# MCU.net
KiCad netlist of a schematic drawn in Altium Designer
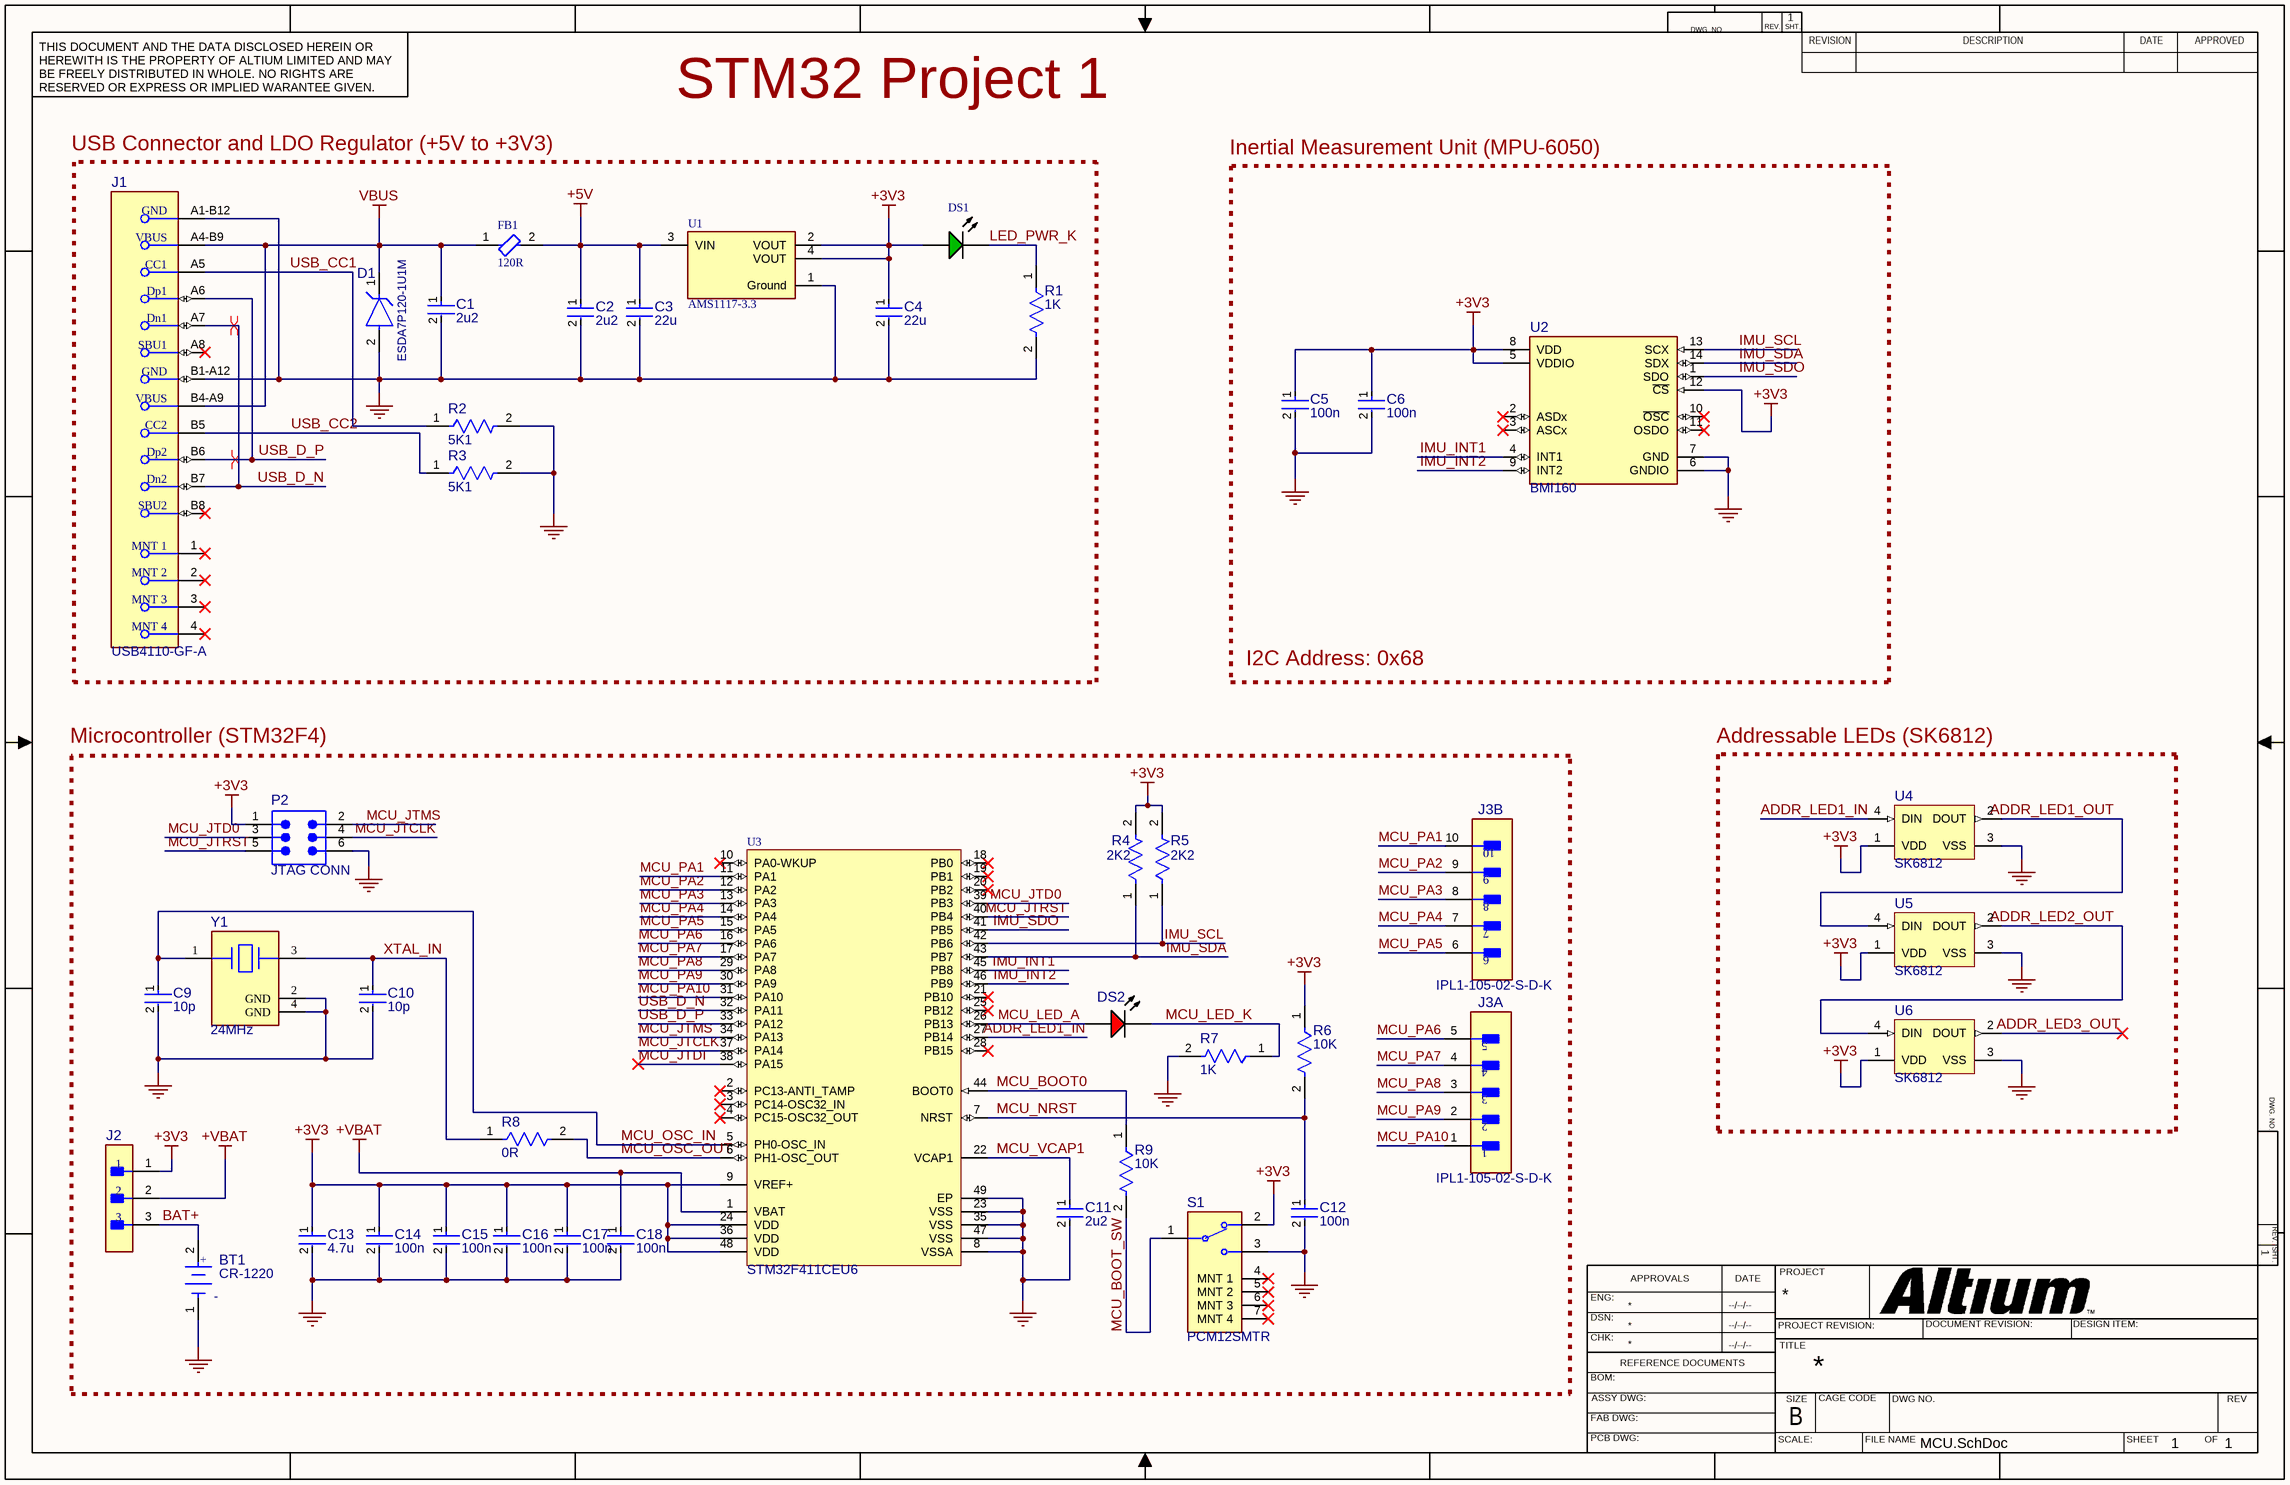
[diagram p0: MCU.SchDoc]

(export (version "E")
  (design (tool "Eeschema 10.0.6"))
  (components
    (comp (ref "BT1")
      (value "CR-1220")
      (footprint "FP-S8411-45R-MFG")
      (description "BATTERY HOLDER COIN 12MM SMD")
      (libsource (lib "Altium Content Vault") (part "60d3b5b901a8747834971d0eb8cf3fd"))
    )
    (comp (ref "C1")
      (value "2u2")
      (footprint "FP-0805-L_2_01_0_2-W_1_25-IPC_B")
      (description "General Purpose Ceramic Capacitor, 0805, 2.2uF, 10%, X5R, 15%, 10V")
      (fields (field (name "VOLTAGE") "10V") (field (name "TOLERANCE") "10%"))
      (libsource (lib "Altium Content Vault") (part "b4654b650e69147ec39a6b967a45e02"))
    )
    (comp (ref "C2")
      (value "2u2")
      (footprint "FP-0805-L_2_01_0_2-W_1_25-IPC_B")
      (description "General Purpose Ceramic Capacitor, 0805, 2.2uF, 10%, X5R, 15%, 10V")
      (fields (field (name "VOLTAGE") "10V") (field (name "TOLERANCE") "10%"))
      (libsource (lib "Altium Content Vault") (part "b4654b650e69147ec39a6b967a45e02"))
    )
    (comp (ref "C3")
      (value "22u")
      (footprint "FP-CC0805-0_85-MFG")
      (description "CAP CER 0.1UF 16V X7R 0805")
      (fields
        (field (name "MANUFACTURER PART NUMBER") "CC0805KRX7R7BB104")
        (field (name "MANUFACTURER") "Yageo")
      )
      (libsource (lib "Altium Content Vault") (part "11868f565c42a9108669ba33697ecf6"))
    )
    (comp (ref "C4")
      (value "22u")
      (footprint "FP-CC0805-0_85-MFG")
      (description "CAP CER 0.1UF 16V X7R 0805")
      (fields
        (field (name "MANUFACTURER PART NUMBER") "CC0805KRX7R7BB104")
        (field (name "MANUFACTURER") "Yageo")
      )
      (libsource (lib "Altium Content Vault") (part "11868f565c42a9108669ba33697ecf6"))
    )
    (comp (ref "C5")
      (value "100n")
      (footprint "FP-CC0805-0_85-MFG")
      (description "CAP CER 0.1UF 16V X7R 0805")
      (fields
        (field (name "MANUFACTURER PART NUMBER") "CC0805KRX7R7BB104")
        (field (name "MANUFACTURER") "Yageo")
      )
      (libsource (lib "Altium Content Vault") (part "11868f565c42a9108669ba33697ecf6"))
    )
    (comp (ref "C6")
      (value "100n")
      (footprint "FP-CC0805-0_85-MFG")
      (description "CAP CER 0.1UF 16V X7R 0805")
      (fields
        (field (name "MANUFACTURER PART NUMBER") "CC0805KRX7R7BB104")
        (field (name "MANUFACTURER") "Yageo")
      )
      (libsource (lib "Altium Content Vault") (part "11868f565c42a9108669ba33697ecf6"))
    )
    (comp (ref "C9")
      (value "10p")
      (footprint "FP-CC0805-0_85-MFG")
      (description "CAP CER 0.1UF 16V X7R 0805")
      (fields
        (field (name "MANUFACTURER PART NUMBER") "CC0805KRX7R7BB104")
        (field (name "MANUFACTURER") "Yageo")
      )
      (libsource (lib "Altium Content Vault") (part "11868f565c42a9108669ba33697ecf6"))
    )
    (comp (ref "C10")
      (value "10p")
      (footprint "FP-CC0805-0_85-MFG")
      (description "CAP CER 0.1UF 16V X7R 0805")
      (fields
        (field (name "MANUFACTURER PART NUMBER") "CC0805KRX7R7BB104")
        (field (name "MANUFACTURER") "Yageo")
      )
      (libsource (lib "Altium Content Vault") (part "11868f565c42a9108669ba33697ecf6"))
    )
    (comp (ref "C11")
      (value "2u2")
      (footprint "FP-0805-L_2_01_0_2-W_1_25-IPC_B")
      (description "General Purpose Ceramic Capacitor, 0805, 2.2uF, 10%, X5R, 15%, 10V")
      (fields (field (name "VOLTAGE") "10V") (field (name "TOLERANCE") "10%"))
      (libsource (lib "Altium Content Vault") (part "b4654b650e69147ec39a6b967a45e02"))
    )
    (comp (ref "C12")
      (value "100n")
      (footprint "FP-CC0805-0_85-MFG")
      (description "CAP CER 0.1UF 16V X7R 0805")
      (fields
        (field (name "MANUFACTURER PART NUMBER") "CC0805KRX7R7BB104")
        (field (name "MANUFACTURER") "Yageo")
      )
      (libsource (lib "Altium Content Vault") (part "11868f565c42a9108669ba33697ecf6"))
    )
    (comp (ref "C13")
      (value "4.7u")
      (footprint "FP-0805-L_2_01_0_2-W_1_25-MFG")
      (description "General Purpose Ceramic Capacitor, 0805, 4.7uF, 10%, X7R, 15%, 16V")
      (fields (field (name "VOLTAGE") "10V") (field (name "TOLERANCE") "10%"))
      (libsource (lib "Altium Content Vault") (part "02cd4be3c70576c341d710602a673aa"))
    )
    (comp (ref "C14")
      (value "100n")
      (footprint "FP-CC0805-0_85-MFG")
      (description "CAP CER 0.1UF 16V X7R 0805")
      (fields
        (field (name "MANUFACTURER PART NUMBER") "CC0805KRX7R7BB104")
        (field (name "MANUFACTURER") "Yageo")
      )
      (libsource (lib "Altium Content Vault") (part "11868f565c42a9108669ba33697ecf6"))
    )
    (comp (ref "C15")
      (value "100n")
      (footprint "FP-CC0805-0_85-MFG")
      (description "CAP CER 0.1UF 16V X7R 0805")
      (fields
        (field (name "MANUFACTURER PART NUMBER") "CC0805KRX7R7BB104")
        (field (name "MANUFACTURER") "Yageo")
      )
      (libsource (lib "Altium Content Vault") (part "11868f565c42a9108669ba33697ecf6"))
    )
    (comp (ref "C16")
      (value "100n")
      (footprint "FP-CC0805-0_85-MFG")
      (description "CAP CER 0.1UF 16V X7R 0805")
      (fields
        (field (name "MANUFACTURER PART NUMBER") "CC0805KRX7R7BB104")
        (field (name "MANUFACTURER") "Yageo")
      )
      (libsource (lib "Altium Content Vault") (part "11868f565c42a9108669ba33697ecf6"))
    )
    (comp (ref "C17")
      (value "100n")
      (footprint "FP-CC0805-0_85-MFG")
      (description "CAP CER 0.1UF 16V X7R 0805")
      (fields
        (field (name "MANUFACTURER PART NUMBER") "CC0805KRX7R7BB104")
        (field (name "MANUFACTURER") "Yageo")
      )
      (libsource (lib "Altium Content Vault") (part "11868f565c42a9108669ba33697ecf6"))
    )
    (comp (ref "C18")
      (value "100n")
      (footprint "FP-CC0805-0_85-MFG")
      (description "CAP CER 0.1UF 16V X7R 0805")
      (fields
        (field (name "MANUFACTURER PART NUMBER") "CC0805KRX7R7BB104")
        (field (name "MANUFACTURER") "Yageo")
      )
      (libsource (lib "Altium Content Vault") (part "11868f565c42a9108669ba33697ecf6"))
    )
    (comp (ref "D1")
      (value "ESDA7P120-1U1M")
      (footprint "FP-QFN1610-MFG")
      (description "TVS DIODE 5.5V 11.5V 1610")
      (fields
        (field (name "MANUFACTURER") "STMicroelectronics")
        (field (name "OCTOPART") "https://octopart.com/esda7p120-1u1m-stmicroelectronics-80927196")
      )
      (libsource (lib "Altium Content Vault") (part "f813f71cba58e380607f5dd3caf9714"))
    )
    (comp (ref "DS1")
      (value "1K")
      (footprint "AVAG-HSMX-C170_V")
      (description "Chip LED, Green, 2.2 V, -40 to 85 degC, 2-Pin SMD, Pb-Free, Tape and Reel")
      (fields (field (name "MANUFACTURER") "Avago"))
      (libsource (lib "Altium Content Vault") (part "LED_GREEN_A1K2-2"))
    )
    (comp (ref "DS2")
      (value "LTST-C170KRKT")
      (footprint "LTST-C170KRKT_V")
      (description "LED Red, 75 mW, 54 mcd, -55 to 85 degC, 2-Pin SMD, RoHS, Tape and Reel")
      (fields (field (name "MANUFACTURER") "Lite-On"))
      (libsource (lib "Altium Content Vault") (part "LED-RED-AK-2"))
    )
    (comp (ref "FB1")
      (value "120R")
      (footprint "FP-BLM21-0_2-t0_85-e0_5-IPC_A")
      (description "FERRITE BEAD 120 OHM 0805 1LN")
      (fields (field (name "TOLERANCE") "25%"))
      (libsource (lib "Altium Content Vault") (part "5f30dd21d616792df468990f7003faa"))
    )
    (comp (ref "J1")
      (value "USB4110-GF-A")
      (footprint "FP-USB4110-GF-A-MFG")
      (description "CONN USB 2.0 TYPE-C R/A SMT")
      (fields
        (field (name "OCTOPART") "https://octopart.com/usb4110-gf-a-gct-103941985")
        (field (name "MANUFACTURER") "GCT")
      )
      (libsource (lib "Altium Content Vault") (part "e23f2b38bb3c3f98e683ebab9ede730"))
    )
    (comp (ref "J2")
      (value "5-146128-1")
      (footprint "FP-5-146128-1-MFG")
      (description "CONN HEADER SMD 3POS 2.54MM")
      (fields
        (field (name "MANUFACTURER") "TE")
        (field (name "OCTOPART") "https://octopart.com/5-146128-1-te+connectivity-40948200")
      )
      (libsource (lib "Altium Content Vault") (part "0d3f023dd272f625e17a2be33dea85f"))
    )
    (comp (ref "J3")
      (value "IPL1-105-02-S-D-K")
      (footprint "FP-IPL1-105-02-S-D-K-0")
      (description "5 Position 2 Row .100\" (2.54 mm) pitch connector")
      (libsource (lib "Altium Content Vault") (part "66d25172edd0fcb6412fc33dd95d2c2"))
    )
    (comp (ref "P2")
      (value "JTAG CONN")
      (footprint "61000621121")
      (libsource (lib "Altium Content Vault") (part "Header_Male_2R_06P"))
    )
    (comp (ref "R1")
      (value "1K")
      (footprint "FP-CRCW0805-e3-IPC_A")
      (description "RES Thick Film, 10kΩ, 1%, 0.125W, 100ppm/°C, 0805")
      (fields (field (name "TOLERANCE") "1%"))
      (libsource (lib "Altium Content Vault") (part "1029c3af85768c4190bb7ad29bc67b5"))
    )
    (comp (ref "R2")
      (value "5K1")
      (footprint "FP-CRCW0805-e3-IPC_A")
      (description "RES Thick Film, 10kΩ, 1%, 0.125W, 100ppm/°C, 0805")
      (fields (field (name "TOLERANCE") "1%"))
      (libsource (lib "Altium Content Vault") (part "1029c3af85768c4190bb7ad29bc67b5"))
    )
    (comp (ref "R3")
      (value "5K1")
      (footprint "FP-CRCW0805-e3-IPC_A")
      (description "RES Thick Film, 10kΩ, 1%, 0.125W, 100ppm/°C, 0805")
      (fields (field (name "TOLERANCE") "1%"))
      (libsource (lib "Altium Content Vault") (part "1029c3af85768c4190bb7ad29bc67b5"))
    )
    (comp (ref "R4")
      (value "2K2")
      (footprint "FP-CRCW0805-e3-IPC_A")
      (description "RES Thick Film, 10kΩ, 1%, 0.125W, 100ppm/°C, 0805")
      (fields (field (name "TOLERANCE") "1%"))
      (libsource (lib "Altium Content Vault") (part "1029c3af85768c4190bb7ad29bc67b5"))
    )
    (comp (ref "R5")
      (value "2K2")
      (footprint "FP-CRCW0805-e3-IPC_A")
      (description "RES Thick Film, 10kΩ, 1%, 0.125W, 100ppm/°C, 0805")
      (fields (field (name "TOLERANCE") "1%"))
      (libsource (lib "Altium Content Vault") (part "1029c3af85768c4190bb7ad29bc67b5"))
    )
    (comp (ref "R6")
      (value "10K")
      (footprint "FP-CRCW0805-e3-IPC_A")
      (description "RES Thick Film, 10kΩ, 1%, 0.125W, 100ppm/°C, 0805")
      (fields (field (name "TOLERANCE") "1%"))
      (libsource (lib "Altium Content Vault") (part "1029c3af85768c4190bb7ad29bc67b5"))
    )
    (comp (ref "R7")
      (value "1K")
      (footprint "FP-CRCW0805-e3-IPC_A")
      (description "RES Thick Film, 10kΩ, 1%, 0.125W, 100ppm/°C, 0805")
      (fields (field (name "TOLERANCE") "1%"))
      (libsource (lib "Altium Content Vault") (part "1029c3af85768c4190bb7ad29bc67b5"))
    )
    (comp (ref "R8")
      (value "0R")
      (footprint "FP-CRCW0805-e3-IPC_A")
      (description "RES Thick Film, 10kΩ, 1%, 0.125W, 100ppm/°C, 0805")
      (fields (field (name "TOLERANCE") "1%"))
      (libsource (lib "Altium Content Vault") (part "1029c3af85768c4190bb7ad29bc67b5"))
    )
    (comp (ref "R9")
      (value "10K")
      (footprint "FP-CRCW0805-e3-IPC_A")
      (description "RES Thick Film, 10kΩ, 1%, 0.125W, 100ppm/°C, 0805")
      (fields (field (name "TOLERANCE") "1%"))
      (libsource (lib "Altium Content Vault") (part "1029c3af85768c4190bb7ad29bc67b5"))
    )
    (comp (ref "S1")
      (value "PCM12SMTR")
      (footprint "FP-PCM12SMTR-MFG")
      (description "SWITCH SLIDE SPDT 300MA 6V")
      (libsource (lib "Altium Content Vault") (part "1a3f67d7e2b5469b171eeab59ffb4d2"))
    )
    (comp (ref "U1")
      (value "AMS1117-3.3")
      (footprint "FP-AMS1117-IPC_C")
      (description "LDO Voltage Regulators 1A, 3.3V")
      (fields
        (field (name "OCTOPART") "https://octopart.com/ams1117-3.3-advanced+monolithic+systems-25899300")
        (field (name "MANUFACTURER") "Advanced Monolithic Systems")
      )
      (libsource (lib "Altium Content Vault") (part "8bdbb5f8e77002000e30dd2845d0354"))
    )
    (comp (ref "U2")
      (value "BMI160")
      (footprint "FP-BMI160-MFG")
      (description "IMU ACCEL/GYRO I2C/SPI 14LGA")
      (libsource (lib "Altium Content Vault") (part "31c3d492c9327b72c063bbae4eb218e"))
    )
    (comp (ref "U3")
      (value "STM32F411CEU6")
      (footprint "STM-UFQFPN48_L")
      (libsource (lib "Altium Content Vault") (part "MC-ARM-STM32F411-UFQFPN48"))
    )
    (comp (ref "U4")
      (value "SK6812")
      (footprint "ADA-RGB-1655_V")
      (fields (field (name "MANUFACTURER") "Adafruit-Industries-LLC"))
      (libsource (lib "Altium Content Vault") (part "ADA-RGB-1655-4"))
    )
    (comp (ref "U5")
      (value "SK6812")
      (footprint "ADA-RGB-1655_V")
      (fields (field (name "MANUFACTURER") "Adafruit-Industries-LLC"))
      (libsource (lib "Altium Content Vault") (part "ADA-RGB-1655-4"))
    )
    (comp (ref "U6")
      (value "SK6812")
      (footprint "ADA-RGB-1655_V")
      (fields (field (name "MANUFACTURER") "Adafruit-Industries-LLC"))
      (libsource (lib "Altium Content Vault") (part "ADA-RGB-1655-4"))
    )
    (comp (ref "Y1")
      (value "24MHz")
      (footprint "FP-ABM8G-MFG")
      (description "Crystal 24MHz ±30ppm (Tol) ±30ppm (Stability) 10pF FUND 60Ω 4-Pin SMD T/R")
      (fields (field (name "TOLERANCE") "30ppm"))
      (libsource (lib "Altium Content Vault") (part "48e526d86b7f2615d98721063c72f49"))
    )
  )
  (nets
    (net (code "1") (name "+3V3") (class "Default")
      (node (ref "C13") (pin "1") (pinfunction "1_1") (pintype "passive"))
      (node (ref "C14") (pin "1") (pinfunction "1_1") (pintype "passive"))
      (node (ref "C15") (pin "1") (pinfunction "1_1") (pintype "passive"))
      (node (ref "C16") (pin "1") (pinfunction "1_1") (pintype "passive"))
      (node (ref "C17") (pin "1") (pinfunction "1_1") (pintype "passive"))
      (node (ref "C4") (pin "1") (pinfunction "1_1") (pintype "passive"))
      (node (ref "C5") (pin "1") (pinfunction "1_1") (pintype "passive"))
      (node (ref "C6") (pin "1") (pinfunction "1_1") (pintype "passive"))
      (node (ref "DS1") (pin "1") (pinfunction "A_1") (pintype "passive"))
      (node (ref "J2") (pin "1") (pinfunction "1_1") (pintype "passive"))
      (node (ref "P2") (pin "1") (pinfunction "1_1") (pintype "passive"))
      (node (ref "R4") (pin "2") (pinfunction "2_2") (pintype "passive"))
      (node (ref "R5") (pin "2") (pinfunction "2_2") (pintype "passive"))
      (node (ref "R6") (pin "1") (pinfunction "1_1") (pintype "passive"))
      (node (ref "S1") (pin "2") (pinfunction "2_2") (pintype "passive"))
      (node (ref "U1") (pin "2") (pinfunction "VOUT_2") (pintype "passive"))
      (node (ref "U1") (pin "4") (pinfunction "VOUT_4") (pintype "passive"))
      (node (ref "U2") (pin "12") (pinfunction "~{CS}_12") (pintype "input"))
      (node (ref "U2") (pin "5") (pinfunction "VDDIO_5") (pintype "power_in"))
      (node (ref "U2") (pin "8") (pinfunction "VDD_8") (pintype "power_in"))
      (node (ref "U3") (pin "24") (pinfunction "VDD_24") (pintype "power_in"))
      (node (ref "U3") (pin "36") (pinfunction "VDD_36") (pintype "power_in"))
      (node (ref "U3") (pin "48") (pinfunction "VDD_48") (pintype "power_in"))
      (node (ref "U3") (pin "9") (pinfunction "VREF+_9") (pintype "power_in"))
      (node (ref "U4") (pin "1") (pinfunction "VDD_1") (pintype "power_in"))
      (node (ref "U5") (pin "1") (pinfunction "VDD_1") (pintype "power_in"))
      (node (ref "U6") (pin "1") (pinfunction "VDD_1") (pintype "power_in"))
    )
    (net (code "2") (name "+5V") (class "Default")
      (node (ref "C2") (pin "1") (pinfunction "1_1") (pintype "passive"))
      (node (ref "C3") (pin "1") (pinfunction "1_1") (pintype "passive"))
      (node (ref "FB1") (pin "2") (pinfunction "2_2") (pintype "passive"))
      (node (ref "U1") (pin "3") (pinfunction "VIN_3") (pintype "power_in"))
    )
    (net (code "3") (name "+VBAT") (class "Default")
      (node (ref "C18") (pin "1") (pinfunction "1_1") (pintype "passive"))
      (node (ref "J2") (pin "2") (pinfunction "2_2") (pintype "passive"))
      (node (ref "U3") (pin "1") (pinfunction "VBAT_1") (pintype "power_in"))
    )
    (net (code "4") (name "/ADDR_LED1_IN") (class "Default")
      (node (ref "U3") (pin "27") (pinfunction "PB14_27") (pintype "bidirectional"))
      (node (ref "U4") (pin "4") (pinfunction "DIN_4") (pintype "input"))
    )
    (net (code "5") (name "/ADDR_LED1_OUT") (class "Default")
      (node (ref "U4") (pin "2") (pinfunction "DOUT_2") (pintype "output"))
      (node (ref "U5") (pin "4") (pinfunction "DIN_4") (pintype "input"))
    )
    (net (code "6") (name "/ADDR_LED2_OUT") (class "Default")
      (node (ref "U5") (pin "2") (pinfunction "DOUT_2") (pintype "output"))
      (node (ref "U6") (pin "4") (pinfunction "DIN_4") (pintype "input"))
    )
    (net (code "7") (name "/ADDR_LED3_OUT") (class "Default")
      (node (ref "U6") (pin "2") (pinfunction "DOUT_2") (pintype "output+no_connect"))
    )
    (net (code "8") (name "/BAT+") (class "Default")
      (node (ref "BT1") (pin "2") (pinfunction "A_2") (pintype "passive"))
      (node (ref "J2") (pin "3") (pinfunction "3_3") (pintype "passive"))
    )
    (net (code "9") (name "/IMU_INT1") (class "Default")
      (node (ref "U2") (pin "4") (pinfunction "INT1_4") (pintype "bidirectional"))
      (node (ref "U3") (pin "45") (pinfunction "PB8_45") (pintype "bidirectional"))
    )
    (net (code "10") (name "/IMU_INT2") (class "Default")
      (node (ref "U2") (pin "9") (pinfunction "INT2_9") (pintype "bidirectional"))
      (node (ref "U3") (pin "46") (pinfunction "PB9_46") (pintype "bidirectional"))
    )
    (net (code "11") (name "/IMU_SCL") (class "Default")
      (node (ref "R5") (pin "1") (pinfunction "1_1") (pintype "passive"))
      (node (ref "U2") (pin "13") (pinfunction "SCX_13") (pintype "input"))
      (node (ref "U3") (pin "42") (pinfunction "PB6_42") (pintype "bidirectional"))
    )
    (net (code "12") (name "/IMU_SDA") (class "Default")
      (node (ref "R4") (pin "1") (pinfunction "1_1") (pintype "passive"))
      (node (ref "U2") (pin "14") (pinfunction "SDX_14") (pintype "bidirectional"))
      (node (ref "U3") (pin "43") (pinfunction "PB7_43") (pintype "bidirectional"))
    )
    (net (code "13") (name "/IMU_SDO") (class "Default")
      (node (ref "U2") (pin "1") (pinfunction "SDO_1") (pintype "bidirectional"))
      (node (ref "U3") (pin "41") (pinfunction "PB5_41") (pintype "bidirectional"))
    )
    (net (code "14") (name "/LED_PWR_K") (class "Default")
      (node (ref "DS1") (pin "2") (pinfunction "K_2") (pintype "passive"))
      (node (ref "R1") (pin "1") (pinfunction "1_1") (pintype "passive"))
    )
    (net (code "15") (name "/MCU_BOOT0") (class "Default")
      (node (ref "R9") (pin "1") (pinfunction "1_1") (pintype "passive"))
      (node (ref "U3") (pin "44") (pinfunction "BOOT0_44") (pintype "input"))
    )
    (net (code "16") (name "/MCU_BOOT_SW") (class "Default")
      (node (ref "R9") (pin "2") (pinfunction "2_2") (pintype "passive"))
      (node (ref "S1") (pin "1") (pinfunction "1_1") (pintype "passive"))
    )
    (net (code "17") (name "/MCU_JTCLK") (class "Default")
      (node (ref "P2") (pin "4") (pinfunction "4_4") (pintype "passive"))
      (node (ref "U3") (pin "37") (pinfunction "PA14_37") (pintype "bidirectional"))
    )
    (net (code "18") (name "/MCU_JTD0") (class "Default")
      (node (ref "P2") (pin "3") (pinfunction "3_3") (pintype "passive"))
      (node (ref "U3") (pin "39") (pinfunction "PB3_39") (pintype "bidirectional"))
    )
    (net (code "19") (name "/MCU_JTDI") (class "Default")
      (node (ref "U3") (pin "38") (pinfunction "PA15_38") (pintype "bidirectional+no_connect"))
    )
    (net (code "20") (name "/MCU_JTMS") (class "Default")
      (node (ref "P2") (pin "2") (pinfunction "2_2") (pintype "passive"))
      (node (ref "U3") (pin "34") (pinfunction "PA13_34") (pintype "bidirectional"))
    )
    (net (code "21") (name "/MCU_JTRST") (class "Default")
      (node (ref "P2") (pin "5") (pinfunction "5_5") (pintype "passive"))
      (node (ref "U3") (pin "40") (pinfunction "PB4_40") (pintype "bidirectional"))
    )
    (net (code "22") (name "/MCU_LED_A") (class "Default")
      (node (ref "DS2") (pin "1") (pinfunction "A_1") (pintype "passive"))
      (node (ref "U3") (pin "26") (pinfunction "PB13_26") (pintype "bidirectional"))
    )
    (net (code "23") (name "/MCU_LED_K") (class "Default")
      (node (ref "DS2") (pin "2") (pinfunction "K_2") (pintype "passive"))
      (node (ref "R7") (pin "1") (pinfunction "1_1") (pintype "passive"))
    )
    (net (code "24") (name "/MCU_NRST") (class "Default")
      (node (ref "C12") (pin "1") (pinfunction "1_1") (pintype "passive"))
      (node (ref "R6") (pin "2") (pinfunction "2_2") (pintype "passive"))
      (node (ref "U3") (pin "7") (pinfunction "NRST_7") (pintype "bidirectional"))
    )
    (net (code "25") (name "/MCU_OSC_IN") (class "Default")
      (node (ref "C9") (pin "1") (pinfunction "1_1") (pintype "passive"))
      (node (ref "U3") (pin "5") (pinfunction "PH0-OSC_IN_5") (pintype "bidirectional"))
      (node (ref "Y1") (pin "1") (pinfunction "1_1") (pintype "passive"))
    )
    (net (code "26") (name "/MCU_OSC_OUT") (class "Default")
      (node (ref "R8") (pin "2") (pinfunction "2_2") (pintype "passive"))
      (node (ref "U3") (pin "6") (pinfunction "PH1-OSC_OUT_6") (pintype "bidirectional"))
    )
    (net (code "27") (name "/MCU_PA1") (class "Default")
      (node (ref "J3") (pin "10") (pinfunction "10_10") (pintype "passive"))
      (node (ref "U3") (pin "11") (pinfunction "PA1_11") (pintype "bidirectional"))
    )
    (net (code "28") (name "/MCU_PA2") (class "Default")
      (node (ref "J3") (pin "9") (pinfunction "9_9") (pintype "passive"))
      (node (ref "U3") (pin "12") (pinfunction "PA2_12") (pintype "bidirectional"))
    )
    (net (code "29") (name "/MCU_PA3") (class "Default")
      (node (ref "J3") (pin "8") (pinfunction "8_8") (pintype "passive"))
      (node (ref "U3") (pin "13") (pinfunction "PA3_13") (pintype "bidirectional"))
    )
    (net (code "30") (name "/MCU_PA4") (class "Default")
      (node (ref "J3") (pin "7") (pinfunction "7_7") (pintype "passive"))
      (node (ref "U3") (pin "14") (pinfunction "PA4_14") (pintype "bidirectional"))
    )
    (net (code "31") (name "/MCU_PA5") (class "Default")
      (node (ref "J3") (pin "6") (pinfunction "6_6") (pintype "passive"))
      (node (ref "U3") (pin "15") (pinfunction "PA5_15") (pintype "bidirectional"))
    )
    (net (code "32") (name "/MCU_PA6") (class "Default")
      (node (ref "J3") (pin "5") (pinfunction "5_5") (pintype "passive"))
      (node (ref "U3") (pin "16") (pinfunction "PA6_16") (pintype "bidirectional"))
    )
    (net (code "33") (name "/MCU_PA7") (class "Default")
      (node (ref "J3") (pin "4") (pinfunction "4_4") (pintype "passive"))
      (node (ref "U3") (pin "17") (pinfunction "PA7_17") (pintype "bidirectional"))
    )
    (net (code "34") (name "/MCU_PA8") (class "Default")
      (node (ref "J3") (pin "3") (pinfunction "3_3") (pintype "passive"))
      (node (ref "U3") (pin "29") (pinfunction "PA8_29") (pintype "bidirectional"))
    )
    (net (code "35") (name "/MCU_PA9") (class "Default")
      (node (ref "J3") (pin "2") (pinfunction "2_2") (pintype "passive"))
      (node (ref "U3") (pin "30") (pinfunction "PA9_30") (pintype "bidirectional"))
    )
    (net (code "36") (name "/MCU_PA10") (class "Default")
      (node (ref "J3") (pin "1") (pinfunction "1_1") (pintype "passive"))
      (node (ref "U3") (pin "31") (pinfunction "PA10_31") (pintype "bidirectional"))
    )
    (net (code "37") (name "/MCU_VCAP1") (class "Default")
      (node (ref "C11") (pin "1") (pinfunction "1_1") (pintype "passive"))
      (node (ref "U3") (pin "22") (pinfunction "VCAP1_22") (pintype "passive"))
    )
    (net (code "38") (name "/USB_CC1") (class "Default")
      (node (ref "J1") (pin "A5") (pinfunction "CC1_A5") (pintype "power_in"))
      (node (ref "R2") (pin "1") (pinfunction "1_1") (pintype "passive"))
    )
    (net (code "39") (name "/USB_CC2") (class "Default")
      (node (ref "J1") (pin "B5") (pinfunction "CC2_B5") (pintype "power_in"))
      (node (ref "R3") (pin "1") (pinfunction "1_1") (pintype "passive"))
    )
    (net (code "40") (name "/USB_D_N") (class "Default")
      (node (ref "J1") (pin "A7") (pinfunction "Dn1_A7") (pintype "bidirectional"))
      (node (ref "J1") (pin "B7") (pinfunction "Dn2_B7") (pintype "bidirectional"))
      (node (ref "U3") (pin "32") (pinfunction "PA11_32") (pintype "bidirectional"))
    )
    (net (code "41") (name "/USB_D_P") (class "Default")
      (node (ref "J1") (pin "A6") (pinfunction "Dp1_A6") (pintype "bidirectional"))
      (node (ref "J1") (pin "B6") (pinfunction "Dp2_B6") (pintype "bidirectional"))
      (node (ref "U3") (pin "33") (pinfunction "PA12_33") (pintype "bidirectional"))
    )
    (net (code "42") (name "/XTAL_IN") (class "Default")
      (node (ref "C10") (pin "1") (pinfunction "1_1") (pintype "passive"))
      (node (ref "R8") (pin "1") (pinfunction "1_1") (pintype "passive"))
      (node (ref "Y1") (pin "3") (pinfunction "3_3") (pintype "passive"))
    )
    (net (code "43") (name "GND") (class "Default")
      (node (ref "BT1") (pin "1") (pinfunction "C_1") (pintype "passive"))
      (node (ref "C1") (pin "2") (pinfunction "2_2") (pintype "passive"))
      (node (ref "C10") (pin "2") (pinfunction "2_2") (pintype "passive"))
      (node (ref "C11") (pin "2") (pinfunction "2_2") (pintype "passive"))
      (node (ref "C12") (pin "2") (pinfunction "2_2") (pintype "passive"))
      (node (ref "C13") (pin "2") (pinfunction "2_2") (pintype "passive"))
      (node (ref "C14") (pin "2") (pinfunction "2_2") (pintype "passive"))
      (node (ref "C15") (pin "2") (pinfunction "2_2") (pintype "passive"))
      (node (ref "C16") (pin "2") (pinfunction "2_2") (pintype "passive"))
      (node (ref "C17") (pin "2") (pinfunction "2_2") (pintype "passive"))
      (node (ref "C18") (pin "2") (pinfunction "2_2") (pintype "passive"))
      (node (ref "C2") (pin "2") (pinfunction "2_2") (pintype "passive"))
      (node (ref "C3") (pin "2") (pinfunction "2_2") (pintype "passive"))
      (node (ref "C4") (pin "2") (pinfunction "2_2") (pintype "passive"))
      (node (ref "C5") (pin "2") (pinfunction "2_2") (pintype "passive"))
      (node (ref "C6") (pin "2") (pinfunction "2_2") (pintype "passive"))
      (node (ref "C9") (pin "2") (pinfunction "2_2") (pintype "passive"))
      (node (ref "D1") (pin "2") (pinfunction "A_2") (pintype "passive"))
      (node (ref "J1") (pin "A1-B12") (pinfunction "GND_A1-B12") (pintype "passive"))
      (node (ref "J1") (pin "B1-A12") (pinfunction "GND_B1-A12") (pintype "bidirectional"))
      (node (ref "P2") (pin "6") (pinfunction "6_6") (pintype "passive"))
      (node (ref "R1") (pin "2") (pinfunction "2_2") (pintype "passive"))
      (node (ref "R2") (pin "2") (pinfunction "2_2") (pintype "passive"))
      (node (ref "R3") (pin "2") (pinfunction "2_2") (pintype "passive"))
      (node (ref "R7") (pin "2") (pinfunction "2_2") (pintype "passive"))
      (node (ref "S1") (pin "3") (pinfunction "3_3") (pintype "passive"))
      (node (ref "U1") (pin "1") (pinfunction "Ground_1") (pintype "power_in"))
      (node (ref "U2") (pin "6") (pinfunction "GNDIO_6") (pintype "power_in"))
      (node (ref "U2") (pin "7") (pinfunction "GND_7") (pintype "power_in"))
      (node (ref "U3") (pin "23") (pinfunction "VSS_23") (pintype "power_in"))
      (node (ref "U3") (pin "35") (pinfunction "VSS_35") (pintype "power_in"))
      (node (ref "U3") (pin "47") (pinfunction "VSS_47") (pintype "power_in"))
      (node (ref "U3") (pin "49") (pinfunction "EP_49") (pintype "power_in"))
      (node (ref "U3") (pin "8") (pinfunction "VSSA_8") (pintype "power_in"))
      (node (ref "U4") (pin "3") (pinfunction "VSS_3") (pintype "power_in"))
      (node (ref "U5") (pin "3") (pinfunction "VSS_3") (pintype "power_in"))
      (node (ref "U6") (pin "3") (pinfunction "VSS_3") (pintype "power_in"))
      (node (ref "Y1") (pin "2") (pinfunction "GND_2") (pintype "power_in"))
      (node (ref "Y1") (pin "4") (pinfunction "GND_4") (pintype "power_in"))
    )
    (net (code "44") (name "VBUS") (class "Default")
      (node (ref "C1") (pin "1") (pinfunction "1_1") (pintype "passive"))
      (node (ref "D1") (pin "1") (pinfunction "C_1") (pintype "passive"))
      (node (ref "FB1") (pin "1") (pinfunction "1_1") (pintype "passive"))
      (node (ref "J1") (pin "A4-B9") (pinfunction "VBUS_A4-B9") (pintype "power_in"))
      (node (ref "J1") (pin "B4-A9") (pinfunction "VBUS_B4-A9") (pintype "power_in"))
    )
    (net (code "45") (name "unconnected-(J1-MNT_1-Pad1)") (class "Default")
      (node (ref "J1") (pin "1") (pinfunction "MNT_1_1") (pintype "passive+no_connect"))
    )
    (net (code "46") (name "unconnected-(J1-MNT_2-Pad2)") (class "Default")
      (node (ref "J1") (pin "2") (pinfunction "MNT_2_2") (pintype "passive+no_connect"))
    )
    (net (code "47") (name "unconnected-(J1-MNT_3-Pad3)") (class "Default")
      (node (ref "J1") (pin "3") (pinfunction "MNT_3_3") (pintype "passive+no_connect"))
    )
    (net (code "48") (name "unconnected-(J1-MNT_4-Pad4)") (class "Default")
      (node (ref "J1") (pin "4") (pinfunction "MNT_4_4") (pintype "passive+no_connect"))
    )
    (net (code "49") (name "unconnected-(J1-SBU1-PadA8)") (class "Default")
      (node (ref "J1") (pin "A8") (pinfunction "SBU1_A8") (pintype "bidirectional+no_connect"))
    )
    (net (code "50") (name "unconnected-(J1-SBU2-PadB8)") (class "Default")
      (node (ref "J1") (pin "B8") (pinfunction "SBU2_B8") (pintype "bidirectional+no_connect"))
    )
    (net (code "51") (name "unconnected-(S1-MNT_1-Pad4)") (class "Default")
      (node (ref "S1") (pin "4") (pinfunction "MNT_1_4") (pintype "passive+no_connect"))
    )
    (net (code "52") (name "unconnected-(S1-MNT_2-Pad5)") (class "Default")
      (node (ref "S1") (pin "5") (pinfunction "MNT_2_5") (pintype "passive+no_connect"))
    )
    (net (code "53") (name "unconnected-(S1-MNT_3-Pad6)") (class "Default")
      (node (ref "S1") (pin "6") (pinfunction "MNT_3_6") (pintype "passive+no_connect"))
    )
    (net (code "54") (name "unconnected-(S1-MNT_4-Pad7)") (class "Default")
      (node (ref "S1") (pin "7") (pinfunction "MNT_4_7") (pintype "passive+no_connect"))
    )
    (net (code "55") (name "unconnected-(U2-ASCx-Pad3)") (class "Default")
      (node (ref "U2") (pin "3") (pinfunction "ASCx_3") (pintype "bidirectional+no_connect"))
    )
    (net (code "56") (name "unconnected-(U2-ASDx-Pad2)") (class "Default")
      (node (ref "U2") (pin "2") (pinfunction "ASDx_2") (pintype "bidirectional+no_connect"))
    )
    (net (code "57") (name "unconnected-(U2-OSDO-Pad11)") (class "Default")
      (node (ref "U2") (pin "11") (pinfunction "OSDO_11") (pintype "bidirectional+no_connect"))
    )
    (net (code "58") (name "unconnected-(U2-~{OSC}-Pad10)") (class "Default")
      (node (ref "U2") (pin "10") (pinfunction "~{OSC}_10") (pintype "bidirectional+no_connect"))
    )
    (net (code "59") (name "unconnected-(U3-PA0-WKUP-Pad10)") (class "Default")
      (node (ref "U3") (pin "10") (pinfunction "PA0-WKUP_10") (pintype "bidirectional+no_connect"))
    )
    (net (code "60") (name "unconnected-(U3-PB0-Pad18)") (class "Default")
      (node (ref "U3") (pin "18") (pinfunction "PB0_18") (pintype "bidirectional+no_connect"))
    )
    (net (code "61") (name "unconnected-(U3-PB1-Pad19)") (class "Default")
      (node (ref "U3") (pin "19") (pinfunction "PB1_19") (pintype "bidirectional+no_connect"))
    )
    (net (code "62") (name "unconnected-(U3-PB2-Pad20)") (class "Default")
      (node (ref "U3") (pin "20") (pinfunction "PB2_20") (pintype "bidirectional+no_connect"))
    )
    (net (code "63") (name "unconnected-(U3-PB10-Pad21)") (class "Default")
      (node (ref "U3") (pin "21") (pinfunction "PB10_21") (pintype "bidirectional+no_connect"))
    )
    (net (code "64") (name "unconnected-(U3-PB12-Pad25)") (class "Default")
      (node (ref "U3") (pin "25") (pinfunction "PB12_25") (pintype "bidirectional+no_connect"))
    )
    (net (code "65") (name "unconnected-(U3-PB15-Pad28)") (class "Default")
      (node (ref "U3") (pin "28") (pinfunction "PB15_28") (pintype "bidirectional+no_connect"))
    )
    (net (code "66") (name "unconnected-(U3-PC13-ANTI_TAMP-Pad2)") (class "Default")
      (node (ref "U3") (pin "2") (pinfunction "PC13-ANTI_TAMP_2") (pintype "bidirectional+no_connect"))
    )
    (net (code "67") (name "unconnected-(U3-PC14-OSC32_IN-Pad3)") (class "Default")
      (node (ref "U3") (pin "3") (pinfunction "PC14-OSC32_IN_3") (pintype "bidirectional+no_connect"))
    )
    (net (code "68") (name "unconnected-(U3-PC15-OSC32_OUT-Pad4)") (class "Default")
      (node (ref "U3") (pin "4") (pinfunction "PC15-OSC32_OUT_4") (pintype "bidirectional+no_connect"))
    )
  )
)
